# VoltageSensorInput.net
KiCad netlist of a schematic drawn in Altium Designer
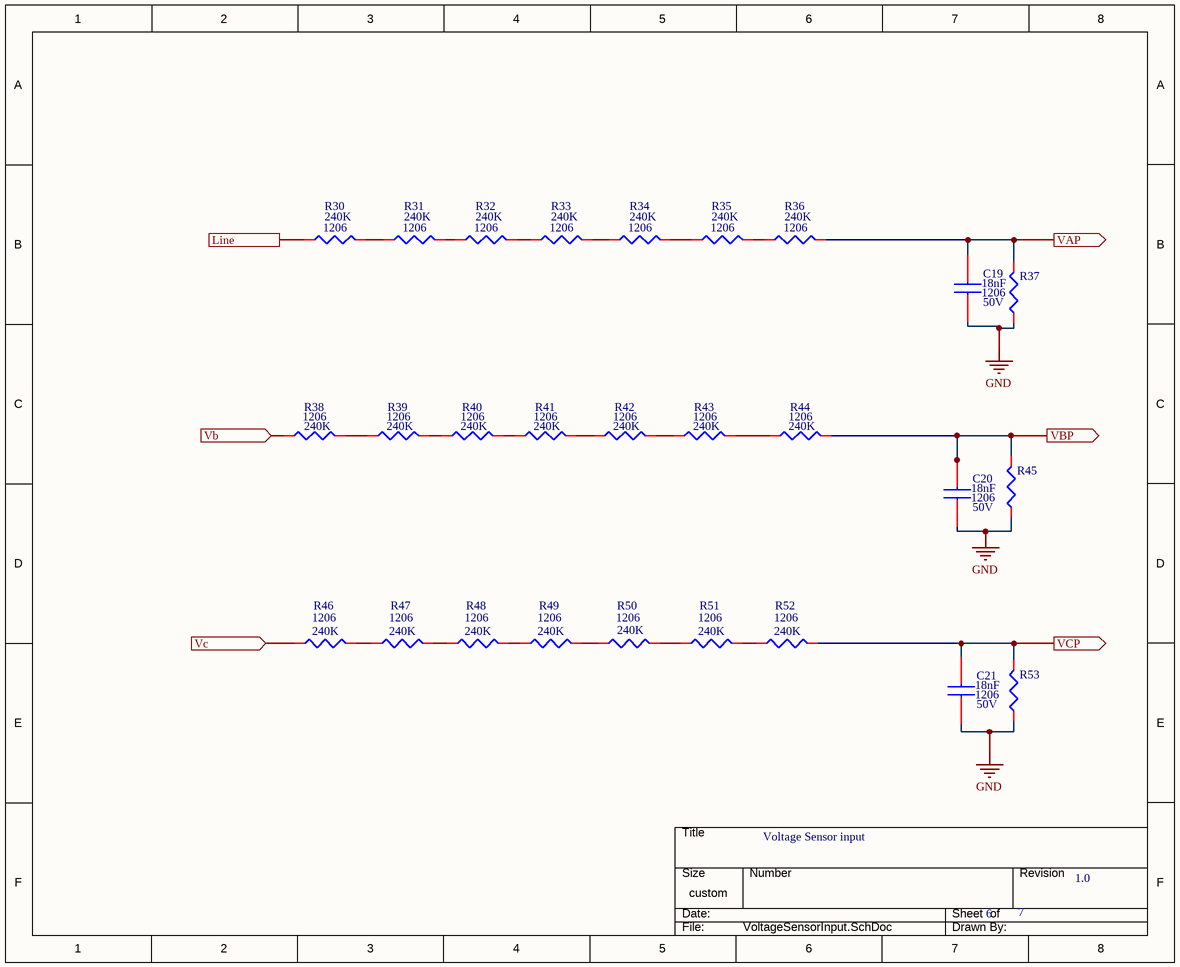
[diagram p0: VoltageSensorInput.SchDoc]

(export (version "E")
  (design (tool "Eeschema 10.0.6"))
  (components
    (comp (ref "C19")
      (value "C1206C183J5RACTU")
      (footprint "CAPC3316X180N")
      (description "Multilayer Ceramic Capacitors MLCC - SMD/SMT 50V 0.018uF X7R 1206 5%")
      (fields
        (field (name "MOUSER PART NUMBER") "80-C1206X224KARAUTO")
        (field (name "MANUFACTURER_PART_NUMBER") "C1206X224KARACAUTO")
        (field (name "SIZE") "1206")
        (field (name "CAPACITANCE") "18nF")
        (field (name "VOLTAGE") "50V")
      )
      (libsource (lib "C1206X224KARACAUTO") (part "C1206X224KARACAUTO"))
    )
    (comp (ref "C20")
      (value "C1206C183J5RACTU")
      (footprint "CAPC3316X180N")
      (description "Multilayer Ceramic Capacitors MLCC - SMD/SMT 50V 0.018uF X7R 1206 5%")
      (fields
        (field (name "MOUSER PART NUMBER") "80-C1206X224KARAUTO")
        (field (name "MANUFACTURER_PART_NUMBER") "C1206X224KARACAUTO")
        (field (name "SIZE") "1206")
        (field (name "CAPACITANCE") "18nF")
        (field (name "VOLTAGE") "50V")
      )
      (libsource (lib "C1206X224KARACAUTO") (part "C1206X224KARACAUTO"))
    )
    (comp (ref "C21")
      (value "C1206C183J5RACTU")
      (footprint "CAPC3316X180N")
      (description "Multilayer Ceramic Capacitors MLCC - SMD/SMT 50V 0.018uF X7R 1206 5%")
      (fields
        (field (name "MOUSER PART NUMBER") "80-C1206X224KARAUTO")
        (field (name "MANUFACTURER_PART_NUMBER") "C1206X224KARACAUTO")
        (field (name "SIZE") "1206")
        (field (name "CAPACITANCE") "18nF")
        (field (name "VOLTAGE") "50V")
      )
      (libsource (lib "C1206X224KARACAUTO") (part "C1206X224KARACAUTO"))
    )
    (comp (ref "R30")
      (value "ERA-8AEB244V")
      (footprint "RESC3216X70N")
      (description "Thin Film Resistors - SMD 1206 240Kohm 0.1% 25ppm")
      (fields
        (field (name "MOUSER PART NUMBER") "667-ERA-8AEB244V")
        (field (name "SIZE") "1206")
        (field (name "RESISTANCE") "240K")
      )
      (libsource (lib "ERA-8AEB244V") (part "ERA-8AEB244V"))
    )
    (comp (ref "R31")
      (value "ERA-8AEB244V")
      (footprint "RESC3216X70N")
      (description "Thin Film Resistors - SMD 1206 240Kohm 0.1% 25ppm")
      (fields
        (field (name "MOUSER PART NUMBER") "667-ERA-8AEB244V")
        (field (name "SIZE") "1206")
        (field (name "RESISTANCE") "240K")
      )
      (libsource (lib "ERA-8AEB244V") (part "ERA-8AEB244V"))
    )
    (comp (ref "R32")
      (value "ERA-8AEB244V")
      (footprint "RESC3216X70N")
      (description "Thin Film Resistors - SMD 1206 240Kohm 0.1% 25ppm")
      (fields
        (field (name "MOUSER PART NUMBER") "667-ERA-8AEB244V")
        (field (name "SIZE") "1206")
        (field (name "RESISTANCE") "240K")
      )
      (libsource (lib "ERA-8AEB244V") (part "ERA-8AEB244V"))
    )
    (comp (ref "R33")
      (value "ERA-8AEB244V")
      (footprint "RESC3216X70N")
      (description "Thin Film Resistors - SMD 1206 240Kohm 0.1% 25ppm")
      (fields
        (field (name "MOUSER PART NUMBER") "667-ERA-8AEB244V")
        (field (name "SIZE") "1206")
        (field (name "RESISTANCE") "240K")
      )
      (libsource (lib "ERA-8AEB244V") (part "ERA-8AEB244V"))
    )
    (comp (ref "R34")
      (value "ERA-8AEB244V")
      (footprint "RESC3216X70N")
      (description "Thin Film Resistors - SMD 1206 240Kohm 0.1% 25ppm")
      (fields
        (field (name "MOUSER PART NUMBER") "667-ERA-8AEB244V")
        (field (name "SIZE") "1206")
        (field (name "RESISTANCE") "240K")
      )
      (libsource (lib "ERA-8AEB244V") (part "ERA-8AEB244V"))
    )
    (comp (ref "R35")
      (value "ERA-8AEB244V")
      (footprint "RESC3216X70N")
      (description "Thin Film Resistors - SMD 1206 240Kohm 0.1% 25ppm")
      (fields
        (field (name "MOUSER PART NUMBER") "667-ERA-8AEB244V")
        (field (name "SIZE") "1206")
        (field (name "RESISTANCE") "240K")
      )
      (libsource (lib "ERA-8AEB244V") (part "ERA-8AEB244V"))
    )
    (comp (ref "R36")
      (value "ERA-8AEB244V")
      (footprint "RESC3216X70N")
      (description "Thin Film Resistors - SMD 1206 240Kohm 0.1% 25ppm")
      (fields
        (field (name "MOUSER PART NUMBER") "667-ERA-8AEB244V")
        (field (name "SIZE") "1206")
        (field (name "RESISTANCE") "240K")
      )
      (libsource (lib "ERA-8AEB244V") (part "ERA-8AEB244V"))
    )
    (comp (ref "R37")
      (value "ERA-6AED102V")
      (footprint "RESC2013X84N")
      (description "Thin Film Resistors - SMD 0805 1000ohms 25ppm 0.5% AEC-Q200")
      (fields (field (name "MOUSER PART NUMBER") "667-ERA-6AED102V"))
      (libsource (lib "ERA-6AED102V") (part "ERA-6AED102V"))
    )
    (comp (ref "R38")
      (value "ERA-8AEB244V")
      (footprint "RESC3216X70N")
      (description "Thin Film Resistors - SMD 1206 240Kohm 0.1% 25ppm")
      (fields
        (field (name "MOUSER PART NUMBER") "667-ERA-8AEB244V")
        (field (name "SIZE") "1206")
        (field (name "RESISTANCE") "240K")
      )
      (libsource (lib "ERA-8AEB244V") (part "ERA-8AEB244V"))
    )
    (comp (ref "R39")
      (value "ERA-8AEB244V")
      (footprint "RESC3216X70N")
      (description "Thin Film Resistors - SMD 1206 240Kohm 0.1% 25ppm")
      (fields
        (field (name "MOUSER PART NUMBER") "667-ERA-8AEB244V")
        (field (name "SIZE") "1206")
        (field (name "RESISTANCE") "240K")
      )
      (libsource (lib "ERA-8AEB244V") (part "ERA-8AEB244V"))
    )
    (comp (ref "R40")
      (value "ERA-8AEB244V")
      (footprint "RESC3216X70N")
      (description "Thin Film Resistors - SMD 1206 240Kohm 0.1% 25ppm")
      (fields
        (field (name "MOUSER PART NUMBER") "667-ERA-8AEB244V")
        (field (name "SIZE") "1206")
        (field (name "RESISTANCE") "240K")
      )
      (libsource (lib "ERA-8AEB244V") (part "ERA-8AEB244V"))
    )
    (comp (ref "R41")
      (value "ERA-8AEB244V")
      (footprint "RESC3216X70N")
      (description "Thin Film Resistors - SMD 1206 240Kohm 0.1% 25ppm")
      (fields
        (field (name "MOUSER PART NUMBER") "667-ERA-8AEB244V")
        (field (name "SIZE") "1206")
        (field (name "RESISTANCE") "240K")
      )
      (libsource (lib "ERA-8AEB244V") (part "ERA-8AEB244V"))
    )
    (comp (ref "R42")
      (value "ERA-8AEB244V")
      (footprint "RESC3216X70N")
      (description "Thin Film Resistors - SMD 1206 240Kohm 0.1% 25ppm")
      (fields
        (field (name "MOUSER PART NUMBER") "667-ERA-8AEB244V")
        (field (name "SIZE") "1206")
        (field (name "RESISTANCE") "240K")
      )
      (libsource (lib "ERA-8AEB244V") (part "ERA-8AEB244V"))
    )
    (comp (ref "R43")
      (value "ERA-8AEB244V")
      (footprint "RESC3216X70N")
      (description "Thin Film Resistors - SMD 1206 240Kohm 0.1% 25ppm")
      (fields
        (field (name "MOUSER PART NUMBER") "667-ERA-8AEB244V")
        (field (name "SIZE") "1206")
        (field (name "RESISTANCE") "240K")
      )
      (libsource (lib "ERA-8AEB244V") (part "ERA-8AEB244V"))
    )
    (comp (ref "R44")
      (value "ERA-8AEB244V")
      (footprint "RESC3216X70N")
      (description "Thin Film Resistors - SMD 1206 240Kohm 0.1% 25ppm")
      (fields
        (field (name "MOUSER PART NUMBER") "667-ERA-8AEB244V")
        (field (name "SIZE") "1206")
        (field (name "RESISTANCE") "240K")
      )
      (libsource (lib "ERA-8AEB244V") (part "ERA-8AEB244V"))
    )
    (comp (ref "R45")
      (value "ERA-6AED102V")
      (footprint "RESC2013X84N")
      (description "Thin Film Resistors - SMD 0805 1000ohms 25ppm 0.5% AEC-Q200")
      (fields (field (name "MOUSER PART NUMBER") "667-ERA-6AED102V"))
      (libsource (lib "ERA-6AED102V") (part "ERA-6AED102V"))
    )
    (comp (ref "R46")
      (value "ERA-8AEB244V")
      (footprint "RESC3216X70N")
      (description "Thin Film Resistors - SMD 1206 240Kohm 0.1% 25ppm")
      (fields
        (field (name "MOUSER PART NUMBER") "667-ERA-8AEB244V")
        (field (name "SIZE") "1206")
        (field (name "RESISTANCE") "240K")
      )
      (libsource (lib "ERA-8AEB244V") (part "ERA-8AEB244V"))
    )
    (comp (ref "R47")
      (value "ERA-8AEB244V")
      (footprint "RESC3216X70N")
      (description "Thin Film Resistors - SMD 1206 240Kohm 0.1% 25ppm")
      (fields
        (field (name "MOUSER PART NUMBER") "667-ERA-8AEB244V")
        (field (name "SIZE") "1206")
        (field (name "RESISTANCE") "240K")
      )
      (libsource (lib "ERA-8AEB244V") (part "ERA-8AEB244V"))
    )
    (comp (ref "R48")
      (value "ERA-8AEB244V")
      (footprint "RESC3216X70N")
      (description "Thin Film Resistors - SMD 1206 240Kohm 0.1% 25ppm")
      (fields
        (field (name "MOUSER PART NUMBER") "667-ERA-8AEB244V")
        (field (name "SIZE") "1206")
        (field (name "RESISTANCE") "240K")
      )
      (libsource (lib "ERA-8AEB244V") (part "ERA-8AEB244V"))
    )
    (comp (ref "R49")
      (value "ERA-8AEB244V")
      (footprint "RESC3216X70N")
      (description "Thin Film Resistors - SMD 1206 240Kohm 0.1% 25ppm")
      (fields
        (field (name "MOUSER PART NUMBER") "667-ERA-8AEB244V")
        (field (name "SIZE") "1206")
        (field (name "RESISTANCE") "240K")
      )
      (libsource (lib "ERA-8AEB244V") (part "ERA-8AEB244V"))
    )
    (comp (ref "R50")
      (value "ERA-8AEB244V")
      (footprint "RESC3216X70N")
      (description "Thin Film Resistors - SMD 1206 240Kohm 0.1% 25ppm")
      (fields
        (field (name "MOUSER PART NUMBER") "667-ERA-8AEB244V")
        (field (name "SIZE") "1206")
        (field (name "RESISTANCE") "240K")
      )
      (libsource (lib "ERA-8AEB244V") (part "ERA-8AEB244V"))
    )
    (comp (ref "R51")
      (value "ERA-8AEB244V")
      (footprint "RESC3216X70N")
      (description "Thin Film Resistors - SMD 1206 240Kohm 0.1% 25ppm")
      (fields
        (field (name "MOUSER PART NUMBER") "667-ERA-8AEB244V")
        (field (name "SIZE") "1206")
        (field (name "RESISTANCE") "240K")
      )
      (libsource (lib "ERA-8AEB244V") (part "ERA-8AEB244V"))
    )
    (comp (ref "R52")
      (value "ERA-8AEB244V")
      (footprint "RESC3216X70N")
      (description "Thin Film Resistors - SMD 1206 240Kohm 0.1% 25ppm")
      (fields
        (field (name "MOUSER PART NUMBER") "667-ERA-8AEB244V")
        (field (name "SIZE") "1206")
        (field (name "RESISTANCE") "240K")
      )
      (libsource (lib "ERA-8AEB244V") (part "ERA-8AEB244V"))
    )
    (comp (ref "R53")
      (value "ERA-6AED102V")
      (footprint "RESC2013X84N")
      (description "Thin Film Resistors - SMD 0805 1000ohms 25ppm 0.5% AEC-Q200")
      (fields (field (name "MOUSER PART NUMBER") "667-ERA-6AED102V"))
      (libsource (lib "ERA-6AED102V") (part "ERA-6AED102V"))
    )
  )
  (nets
    (net (code "1") (name "/Line") (class "Default")
      (node (ref "R30") (pin "2") (pinfunction "2_2") (pintype "passive"))
    )
    (net (code "2") (name "/VAP") (class "Default")
      (node (ref "C19") (pin "1") (pinfunction "1_1") (pintype "passive"))
      (node (ref "R36") (pin "1") (pinfunction "1_1") (pintype "passive"))
      (node (ref "R37") (pin "1") (pinfunction "1_1") (pintype "passive"))
    )
    (net (code "3") (name "/VBP") (class "Default")
      (node (ref "C20") (pin "1") (pinfunction "1_1") (pintype "passive"))
      (node (ref "R44") (pin "1") (pinfunction "1_1") (pintype "passive"))
      (node (ref "R45") (pin "1") (pinfunction "1_1") (pintype "passive"))
    )
    (net (code "4") (name "/VCP") (class "Default")
      (node (ref "C21") (pin "1") (pinfunction "1_1") (pintype "passive"))
      (node (ref "R52") (pin "1") (pinfunction "1_1") (pintype "passive"))
      (node (ref "R53") (pin "1") (pinfunction "1_1") (pintype "passive"))
    )
    (net (code "5") (name "/Vb") (class "Default")
      (node (ref "R38") (pin "2") (pinfunction "2_2") (pintype "passive"))
    )
    (net (code "6") (name "/Vc") (class "Default")
      (node (ref "R46") (pin "2") (pinfunction "2_2") (pintype "passive"))
    )
    (net (code "7") (name "GND") (class "Default")
      (node (ref "C19") (pin "2") (pinfunction "2_2") (pintype "passive"))
      (node (ref "C20") (pin "2") (pinfunction "2_2") (pintype "passive"))
      (node (ref "C21") (pin "2") (pinfunction "2_2") (pintype "passive"))
      (node (ref "R37") (pin "2") (pinfunction "2_2") (pintype "passive"))
      (node (ref "R45") (pin "2") (pinfunction "2_2") (pintype "passive"))
      (node (ref "R53") (pin "2") (pinfunction "2_2") (pintype "passive"))
    )
    (net (code "8") (name "Net-(R30-Pad1)") (class "Default")
      (node (ref "R30") (pin "1") (pinfunction "1_1") (pintype "passive"))
      (node (ref "R31") (pin "2") (pinfunction "2_2") (pintype "passive"))
    )
    (net (code "9") (name "Net-(R31-Pad1)") (class "Default")
      (node (ref "R31") (pin "1") (pinfunction "1_1") (pintype "passive"))
      (node (ref "R32") (pin "2") (pinfunction "2_2") (pintype "passive"))
    )
    (net (code "10") (name "Net-(R32-Pad1)") (class "Default")
      (node (ref "R32") (pin "1") (pinfunction "1_1") (pintype "passive"))
      (node (ref "R33") (pin "2") (pinfunction "2_2") (pintype "passive"))
    )
    (net (code "11") (name "Net-(R33-Pad1)") (class "Default")
      (node (ref "R33") (pin "1") (pinfunction "1_1") (pintype "passive"))
      (node (ref "R34") (pin "2") (pinfunction "2_2") (pintype "passive"))
    )
    (net (code "12") (name "Net-(R34-Pad1)") (class "Default")
      (node (ref "R34") (pin "1") (pinfunction "1_1") (pintype "passive"))
      (node (ref "R35") (pin "2") (pinfunction "2_2") (pintype "passive"))
    )
    (net (code "13") (name "Net-(R35-Pad1)") (class "Default")
      (node (ref "R35") (pin "1") (pinfunction "1_1") (pintype "passive"))
      (node (ref "R36") (pin "2") (pinfunction "2_2") (pintype "passive"))
    )
    (net (code "14") (name "Net-(R38-Pad1)") (class "Default")
      (node (ref "R38") (pin "1") (pinfunction "1_1") (pintype "passive"))
      (node (ref "R39") (pin "2") (pinfunction "2_2") (pintype "passive"))
    )
    (net (code "15") (name "Net-(R39-Pad1)") (class "Default")
      (node (ref "R39") (pin "1") (pinfunction "1_1") (pintype "passive"))
      (node (ref "R40") (pin "2") (pinfunction "2_2") (pintype "passive"))
    )
    (net (code "16") (name "Net-(R40-Pad1)") (class "Default")
      (node (ref "R40") (pin "1") (pinfunction "1_1") (pintype "passive"))
      (node (ref "R41") (pin "2") (pinfunction "2_2") (pintype "passive"))
    )
    (net (code "17") (name "Net-(R41-Pad1)") (class "Default")
      (node (ref "R41") (pin "1") (pinfunction "1_1") (pintype "passive"))
      (node (ref "R42") (pin "2") (pinfunction "2_2") (pintype "passive"))
    )
    (net (code "18") (name "Net-(R42-Pad1)") (class "Default")
      (node (ref "R42") (pin "1") (pinfunction "1_1") (pintype "passive"))
      (node (ref "R43") (pin "2") (pinfunction "2_2") (pintype "passive"))
    )
    (net (code "19") (name "Net-(R43-Pad1)") (class "Default")
      (node (ref "R43") (pin "1") (pinfunction "1_1") (pintype "passive"))
      (node (ref "R44") (pin "2") (pinfunction "2_2") (pintype "passive"))
    )
    (net (code "20") (name "Net-(R46-Pad1)") (class "Default")
      (node (ref "R46") (pin "1") (pinfunction "1_1") (pintype "passive"))
      (node (ref "R47") (pin "2") (pinfunction "2_2") (pintype "passive"))
    )
    (net (code "21") (name "Net-(R47-Pad1)") (class "Default")
      (node (ref "R47") (pin "1") (pinfunction "1_1") (pintype "passive"))
      (node (ref "R48") (pin "2") (pinfunction "2_2") (pintype "passive"))
    )
    (net (code "22") (name "Net-(R48-Pad1)") (class "Default")
      (node (ref "R48") (pin "1") (pinfunction "1_1") (pintype "passive"))
      (node (ref "R49") (pin "2") (pinfunction "2_2") (pintype "passive"))
    )
    (net (code "23") (name "Net-(R49-Pad1)") (class "Default")
      (node (ref "R49") (pin "1") (pinfunction "1_1") (pintype "passive"))
      (node (ref "R50") (pin "2") (pinfunction "2_2") (pintype "passive"))
    )
    (net (code "24") (name "Net-(R50-Pad1)") (class "Default")
      (node (ref "R50") (pin "1") (pinfunction "1_1") (pintype "passive"))
      (node (ref "R51") (pin "2") (pinfunction "2_2") (pintype "passive"))
    )
    (net (code "25") (name "Net-(R51-Pad1)") (class "Default")
      (node (ref "R51") (pin "1") (pinfunction "1_1") (pintype "passive"))
      (node (ref "R52") (pin "2") (pinfunction "2_2") (pintype "passive"))
    )
  )
)
